# comma_access_point.net
KiCad netlist of a schematic drawn in EAGLE
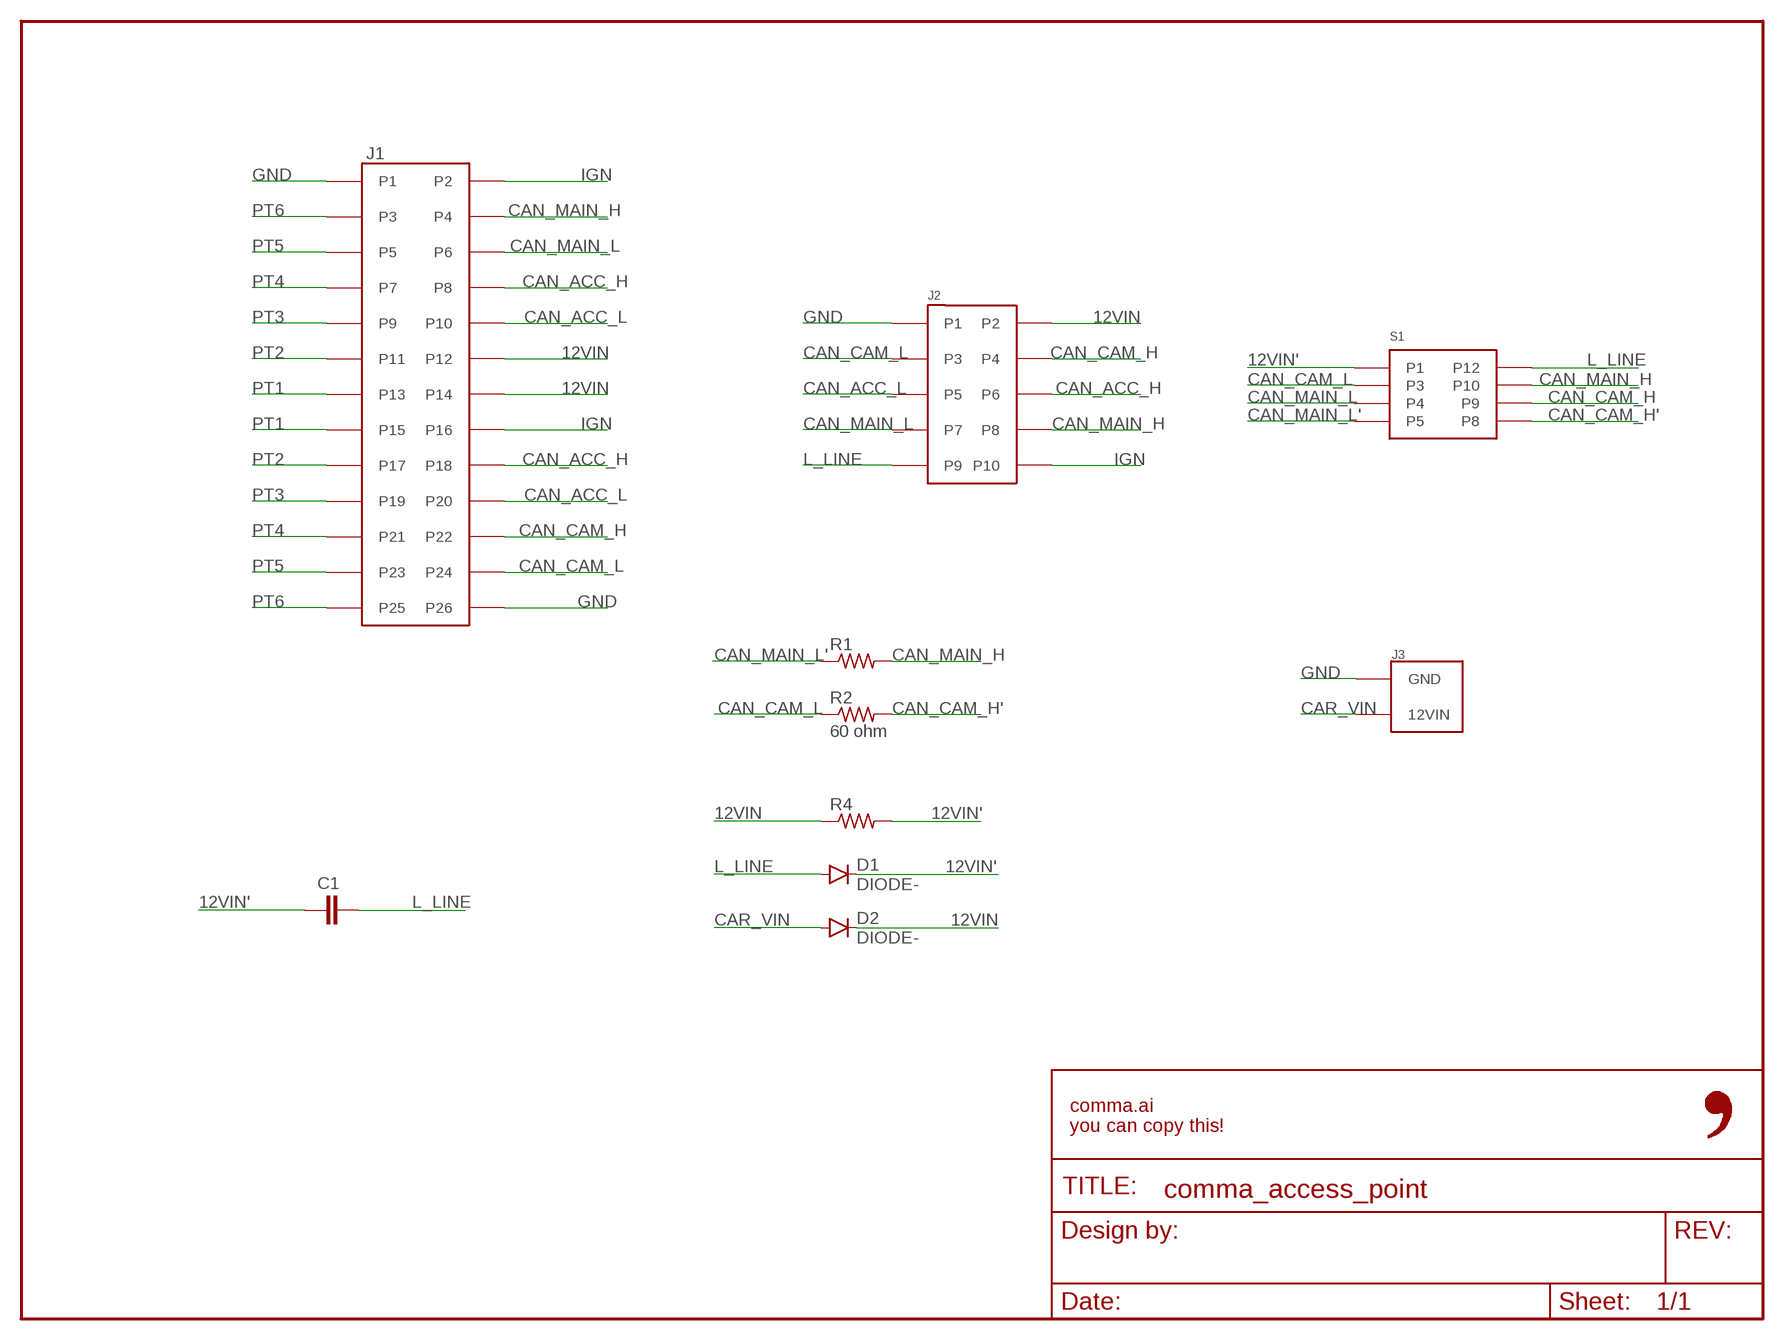
[diagram p0: schematic, sheet 1]

(export (version "E")
  (design (tool "Eeschema 10.0.6"))
  (components
    (comp (ref "C1")
      (value "C0805")
      (footprint "eagle-import:0805-C")
      (libsource (lib "eagle-import") (part "C0805"))
    )
    (comp (ref "D1")
      (value "DIODE-")
      (footprint "eagle-import:DO-214")
      (libsource (lib "eagle-import") (part "DIODE-"))
    )
    (comp (ref "D2")
      (value "DIODE-")
      (footprint "eagle-import:DO-214")
      (libsource (lib "eagle-import") (part "DIODE-"))
    )
    (comp (ref "FRAME1")
      (value "FRAME-LETTER-OPENNO_PACKAGE")
      (footprint "eagle-import:DUMMY")
      (fields (field (name "DESIGNER") "Nobody"))
      (libsource (lib "eagle-import") (part "FRAME-LETTER-OPENNO_PACKAGE"))
    )
    (comp (ref "J1")
      (value "5018762640")
      (footprint "eagle-import:5018762640")
      (libsource (lib "eagle-import") (part "5018762640"))
    )
    (comp (ref "J2")
      (value "5018761040")
      (footprint "eagle-import:5018761040")
      (libsource (lib "eagle-import") (part "5018761040"))
    )
    (comp (ref "J3")
      (value "3-794618-2")
      (footprint "eagle-import:3-794618-2")
      (libsource (lib "eagle-import") (part "3-794618-2"))
    )
    (comp (ref "R1")
      (value "R0402")
      (footprint "eagle-import:0402-R")
      (libsource (lib "eagle-import") (part "R0402"))
    )
    (comp (ref "R2")
      (value "60 ohm")
      (footprint "eagle-import:0402-R")
      (libsource (lib "eagle-import") (part "R0402"))
    )
    (comp (ref "R4")
      (value "R0402")
      (footprint "eagle-import:0402-R")
      (libsource (lib "eagle-import") (part "R0402"))
    )
    (comp (ref "S1")
      (value "G6S-2G-DC12")
      (footprint "eagle-import:G6S-26-DC12")
      (libsource (lib "eagle-import") (part "G6S-2G-DC12"))
    )
  )
  (nets
    (net (code "1") (name "/12VIN") (class "Default")
      (node (ref "D2") (pin "1") (pinfunction "C_1") (pintype "passive"))
      (node (ref "J1") (pin "P12") (pinfunction "P12_P12") (pintype "bidirectional"))
      (node (ref "J1") (pin "P14") (pinfunction "P14_P14") (pintype "bidirectional"))
      (node (ref "J2") (pin "P2") (pinfunction "P2_P2") (pintype "bidirectional"))
      (node (ref "R4") (pin "1") (pinfunction "1_1") (pintype "passive"))
    )
    (net (code "2") (name "/12VIN'") (class "Default")
      (node (ref "C1") (pin "1") (pinfunction "1_1") (pintype "passive"))
      (node (ref "D1") (pin "1") (pinfunction "C_1") (pintype "passive"))
      (node (ref "R4") (pin "2") (pinfunction "2_2") (pintype "passive"))
      (node (ref "S1") (pin "P1") (pinfunction "P1_P1") (pintype "bidirectional"))
    )
    (net (code "3") (name "/CAN_ACC_H") (class "Default")
      (node (ref "J1") (pin "P18") (pinfunction "P18_P18") (pintype "bidirectional"))
      (node (ref "J1") (pin "P8") (pinfunction "P8_P8") (pintype "bidirectional"))
      (node (ref "J2") (pin "P6") (pinfunction "P6_P6") (pintype "bidirectional"))
    )
    (net (code "4") (name "/CAN_ACC_L") (class "Default")
      (node (ref "J1") (pin "P10") (pinfunction "P10_P10") (pintype "bidirectional"))
      (node (ref "J1") (pin "P20") (pinfunction "P20_P20") (pintype "bidirectional"))
      (node (ref "J2") (pin "P5") (pinfunction "P5_P5") (pintype "bidirectional"))
    )
    (net (code "5") (name "/CAN_CAM_H") (class "Default")
      (node (ref "J1") (pin "P22") (pinfunction "P22_P22") (pintype "bidirectional"))
      (node (ref "J2") (pin "P4") (pinfunction "P4_P4") (pintype "bidirectional"))
      (node (ref "S1") (pin "P9") (pinfunction "P9_P9") (pintype "bidirectional"))
    )
    (net (code "6") (name "/CAN_CAM_H'") (class "Default")
      (node (ref "R2") (pin "2") (pinfunction "2_2") (pintype "passive"))
      (node (ref "S1") (pin "P8") (pinfunction "P8_P8") (pintype "bidirectional"))
    )
    (net (code "7") (name "/CAN_CAM_L") (class "Default")
      (node (ref "J1") (pin "P24") (pinfunction "P24_P24") (pintype "bidirectional"))
      (node (ref "J2") (pin "P3") (pinfunction "P3_P3") (pintype "bidirectional"))
      (node (ref "R2") (pin "1") (pinfunction "1_1") (pintype "passive"))
      (node (ref "S1") (pin "P3") (pinfunction "P3_P3") (pintype "bidirectional"))
    )
    (net (code "8") (name "/CAN_MAIN_H") (class "Default")
      (node (ref "J1") (pin "P4") (pinfunction "P4_P4") (pintype "bidirectional"))
      (node (ref "J2") (pin "P8") (pinfunction "P8_P8") (pintype "bidirectional"))
      (node (ref "R1") (pin "2") (pinfunction "2_2") (pintype "passive"))
      (node (ref "S1") (pin "P10") (pinfunction "P10_P10") (pintype "bidirectional"))
    )
    (net (code "9") (name "/CAN_MAIN_L") (class "Default")
      (node (ref "J1") (pin "P6") (pinfunction "P6_P6") (pintype "bidirectional"))
      (node (ref "J2") (pin "P7") (pinfunction "P7_P7") (pintype "bidirectional"))
      (node (ref "S1") (pin "P4") (pinfunction "P4_P4") (pintype "bidirectional"))
    )
    (net (code "10") (name "/CAN_MAIN_L'") (class "Default")
      (node (ref "R1") (pin "1") (pinfunction "1_1") (pintype "passive"))
      (node (ref "S1") (pin "P5") (pinfunction "P5_P5") (pintype "bidirectional"))
    )
    (net (code "11") (name "/CAR_VIN") (class "Default")
      (node (ref "D2") (pin "2") (pinfunction "A_2") (pintype "passive"))
      (node (ref "J3") (pin "12VIN") (pinfunction "12VIN_12VIN") (pintype "bidirectional"))
    )
    (net (code "12") (name "/GND") (class "Default")
      (node (ref "J1") (pin "P1") (pinfunction "P1_P1") (pintype "bidirectional"))
      (node (ref "J1") (pin "P26") (pinfunction "P26_P26") (pintype "bidirectional"))
      (node (ref "J2") (pin "P1") (pinfunction "P1_P1") (pintype "bidirectional"))
      (node (ref "J3") (pin "GND") (pinfunction "GND_GND") (pintype "bidirectional"))
    )
    (net (code "13") (name "/IGN") (class "Default")
      (node (ref "J1") (pin "P16") (pinfunction "P16_P16") (pintype "bidirectional"))
      (node (ref "J1") (pin "P2") (pinfunction "P2_P2") (pintype "bidirectional"))
      (node (ref "J2") (pin "P10") (pinfunction "P10_P10") (pintype "bidirectional"))
    )
    (net (code "14") (name "/L_LINE") (class "Default")
      (node (ref "C1") (pin "2") (pinfunction "2_2") (pintype "passive"))
      (node (ref "D1") (pin "2") (pinfunction "A_2") (pintype "passive"))
      (node (ref "J2") (pin "P9") (pinfunction "P9_P9") (pintype "bidirectional"))
      (node (ref "S1") (pin "P12") (pinfunction "P12_P12") (pintype "bidirectional"))
    )
    (net (code "15") (name "/PT1") (class "Default")
      (node (ref "J1") (pin "P13") (pinfunction "P13_P13") (pintype "bidirectional"))
      (node (ref "J1") (pin "P15") (pinfunction "P15_P15") (pintype "bidirectional"))
    )
    (net (code "16") (name "/PT2") (class "Default")
      (node (ref "J1") (pin "P11") (pinfunction "P11_P11") (pintype "bidirectional"))
      (node (ref "J1") (pin "P17") (pinfunction "P17_P17") (pintype "bidirectional"))
    )
    (net (code "17") (name "/PT3") (class "Default")
      (node (ref "J1") (pin "P19") (pinfunction "P19_P19") (pintype "bidirectional"))
      (node (ref "J1") (pin "P9") (pinfunction "P9_P9") (pintype "bidirectional"))
    )
    (net (code "18") (name "/PT4") (class "Default")
      (node (ref "J1") (pin "P21") (pinfunction "P21_P21") (pintype "bidirectional"))
      (node (ref "J1") (pin "P7") (pinfunction "P7_P7") (pintype "bidirectional"))
    )
    (net (code "19") (name "/PT5") (class "Default")
      (node (ref "J1") (pin "P23") (pinfunction "P23_P23") (pintype "bidirectional"))
      (node (ref "J1") (pin "P5") (pinfunction "P5_P5") (pintype "bidirectional"))
    )
    (net (code "20") (name "/PT6") (class "Default")
      (node (ref "J1") (pin "P25") (pinfunction "P25_P25") (pintype "bidirectional"))
      (node (ref "J1") (pin "P3") (pinfunction "P3_P3") (pintype "bidirectional"))
    )
  )
)
